# cb_v0.net
KiCad netlist of a schematic drawn in Altium Designer
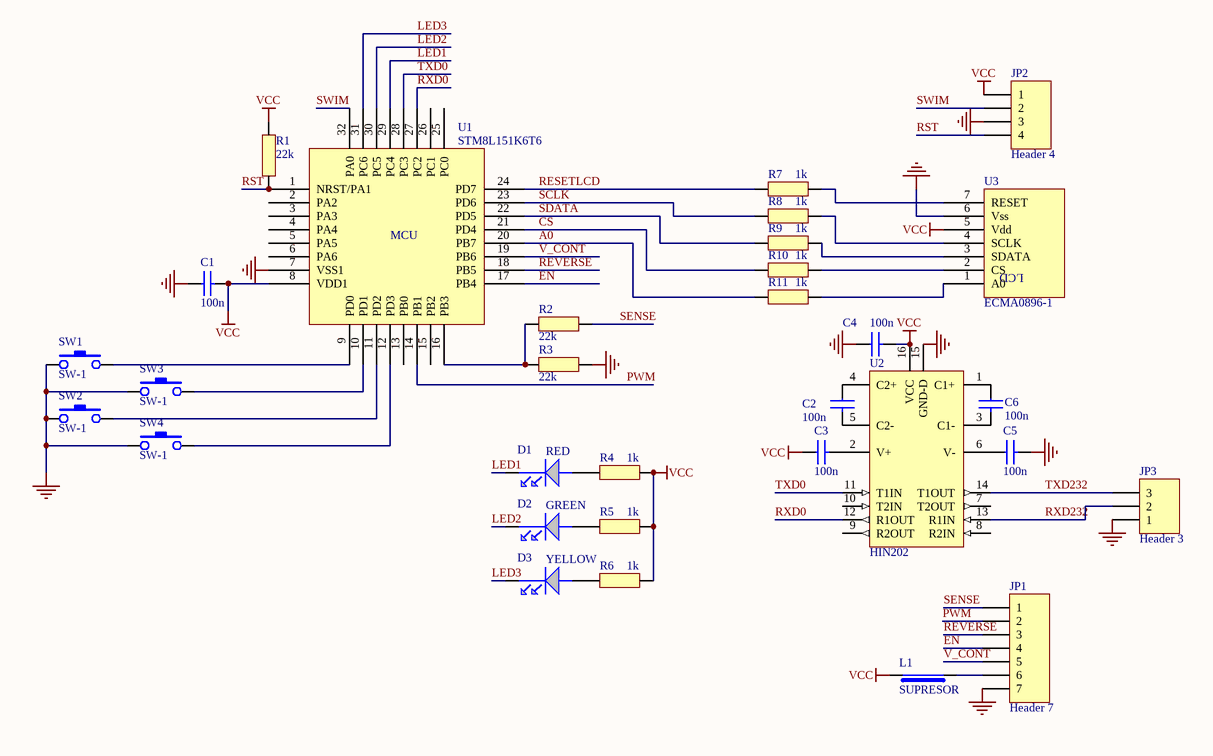
[diagram p0: cb_v0.SchDoc]

(export (version "E")
  (design (tool "Eeschema 10.0.6"))
  (components
    (comp (ref "C1") (value "100n") (footprint "C-0805") (libsource (lib "RCS-Discret") (part "C")))
    (comp (ref "C2") (value "100n") (footprint "C-0805") (libsource (lib "RCS-Discret") (part "C")))
    (comp (ref "C3") (value "100n") (footprint "C-0805") (libsource (lib "RCS-Discret") (part "C")))
    (comp (ref "C4") (value "100n") (footprint "C-0805") (libsource (lib "RCS-Discret") (part "C")))
    (comp (ref "C5") (value "100n") (footprint "C-0805") (libsource (lib "RCS-Discret") (part "C")))
    (comp (ref "C6") (value "100n") (footprint "C-0805") (libsource (lib "RCS-Discret") (part "C")))
    (comp (ref "D1") (value "RED") (footprint "LED-DIP-1") (libsource (lib "RCS-Discret") (part "LED")))
    (comp (ref "D2") (value "GREEN") (footprint "LED-DIP-1") (libsource (lib "RCS-Discret") (part "LED")))
    (comp (ref "D3") (value "YELLOW") (footprint "LED-DIP-1") (libsource (lib "RCS-Discret") (part "LED")))
    (comp (ref "JP1")
      (value "Header 7")
      (footprint "HDR1X7")
      (description "Header, 7-Pin")
      (fields (field (name "PUBLISHER") "Altium Limited"))
      (libsource (lib "Miscellaneous Connectors") (part "Header 7"))
    )
    (comp (ref "JP2")
      (value "Header 4")
      (footprint "HDR1X4")
      (description "Header, 4-Pin")
      (fields (field (name "PUBLISHER") "Altium Limited"))
      (libsource (lib "Miscellaneous Connectors") (part "Header 4"))
    )
    (comp (ref "JP3")
      (value "Header 3")
      (footprint "HDR1X3")
      (description "Header, 3-Pin")
      (fields (field (name "PUBLISHER") "Altium Limited"))
      (libsource (lib "Miscellaneous Connectors") (part "Header 3"))
    )
    (comp (ref "L1")
      (value "SUPRESOR")
      (footprint "R-1206")
      (libsource (lib "RCS-Discret") (part "SUPRESOR"))
    )
    (comp (ref "R1") (value "22k") (footprint "R-0805") (libsource (lib "") (part "R_3")))
    (comp (ref "R2") (value "22k") (footprint "R-0805") (libsource (lib "") (part "R_1")))
    (comp (ref "R3") (value "22k") (footprint "R-0805") (libsource (lib "") (part "R_2")))
    (comp (ref "R4") (value "1k") (footprint "R-0805") (libsource (lib "") (part "R_2")))
    (comp (ref "R5") (value "1k") (footprint "R-0805") (libsource (lib "") (part "R_2")))
    (comp (ref "R6") (value "1k") (footprint "R-0805") (libsource (lib "") (part "R_2")))
    (comp (ref "R7") (value "1k") (footprint "R-0805") (libsource (lib "RCS-Discret") (part "R")))
    (comp (ref "R8") (value "1k") (footprint "R-0805") (libsource (lib "RCS-Discret") (part "R")))
    (comp (ref "R9") (value "1k") (footprint "R-0805") (libsource (lib "RCS-Discret") (part "R")))
    (comp (ref "R10") (value "1k") (footprint "R-0805") (libsource (lib "RCS-Discret") (part "R")))
    (comp (ref "R11") (value "1k") (footprint "R-0805") (libsource (lib "RCS-Discret") (part "R")))
    (comp (ref "SW1")
      (value "SW-1")
      (footprint "SW2mini")
      (libsource (lib "RCS-Connect&pushe") (part "SW-1"))
    )
    (comp (ref "SW2")
      (value "SW-1")
      (footprint "SW2mini")
      (libsource (lib "RCS-Connect&pushe") (part "SW-1"))
    )
    (comp (ref "SW3")
      (value "SW-1")
      (footprint "SW2mini")
      (libsource (lib "RCS-Connect&pushe") (part "SW-1"))
    )
    (comp (ref "SW4")
      (value "SW-1")
      (footprint "SW2mini")
      (libsource (lib "RCS-Connect&pushe") (part "SW-1"))
    )
    (comp (ref "U1")
      (value "STM8L151K6T6")
      (footprint "QFP32")
      (libsource (lib "RCS-IMS") (part "STM32L151"))
    )
    (comp (ref "U2")
      (value "HIN202")
      (footprint "SO16-(SOT-109-1)")
      (description "RS232 driver")
      (libsource (lib "RCS-IMS") (part "HIN202"))
    )
    (comp (ref "U3")
      (value "ECMA0896-1")
      (footprint "ECMA0896")
      (libsource (lib "RCS-IMS") (part "ECMA0896"))
    )
  )
  (nets
    (net (code "1") (name "/A0") (class "Default")
      (node (ref "R11") (pin "1") (pinfunction "1_1") (pintype "passive"))
      (node (ref "U1") (pin "20") (pinfunction "PB7_20") (pintype "passive"))
    )
    (net (code "2") (name "/CS") (class "Default")
      (node (ref "R10") (pin "1") (pinfunction "1_1") (pintype "passive"))
      (node (ref "U1") (pin "21") (pinfunction "PD4_21") (pintype "passive"))
    )
    (net (code "3") (name "/EN") (class "Default")
      (node (ref "JP1") (pin "4") (pinfunction "4_4") (pintype "passive"))
      (node (ref "U1") (pin "17") (pinfunction "PB4_17") (pintype "passive"))
    )
    (net (code "4") (name "/LED1") (class "Default")
      (node (ref "D1") (pin "K") (pinfunction "CATHODE_K") (pintype "passive"))
      (node (ref "U1") (pin "29") (pinfunction "PC4_29") (pintype "passive"))
    )
    (net (code "5") (name "/LED2") (class "Default")
      (node (ref "D2") (pin "K") (pinfunction "CATHODE_K") (pintype "passive"))
      (node (ref "U1") (pin "30") (pinfunction "PC5_30") (pintype "passive"))
    )
    (net (code "6") (name "/LED3") (class "Default")
      (node (ref "D3") (pin "K") (pinfunction "CATHODE_K") (pintype "passive"))
      (node (ref "U1") (pin "31") (pinfunction "PC6_31") (pintype "passive"))
    )
    (net (code "7") (name "/PWM") (class "Default")
      (node (ref "JP1") (pin "2") (pinfunction "2_2") (pintype "passive"))
      (node (ref "U1") (pin "14") (pinfunction "PB1_14") (pintype "passive"))
    )
    (net (code "8") (name "/RESETLCD") (class "Default")
      (node (ref "R7") (pin "1") (pinfunction "1_1") (pintype "passive"))
      (node (ref "U1") (pin "24") (pinfunction "PD7_24") (pintype "passive"))
    )
    (net (code "9") (name "/REVERSE") (class "Default")
      (node (ref "JP1") (pin "3") (pinfunction "3_3") (pintype "passive"))
      (node (ref "U1") (pin "18") (pinfunction "PB5_18") (pintype "passive"))
    )
    (net (code "10") (name "/RST") (class "Default")
      (node (ref "JP2") (pin "4") (pinfunction "4_4") (pintype "passive"))
      (node (ref "R1") (pin "2") (pinfunction "2_2") (pintype "passive"))
      (node (ref "U1") (pin "1") (pinfunction "NRST/PA1_1") (pintype "passive"))
    )
    (net (code "11") (name "/RXD0") (class "Default")
      (node (ref "U1") (pin "27") (pinfunction "PC2_27") (pintype "passive"))
      (node (ref "U2") (pin "12") (pinfunction "R1OUT_12") (pintype "output"))
    )
    (net (code "12") (name "/RXD232") (class "Default")
      (node (ref "JP3") (pin "2") (pinfunction "2_2") (pintype "passive"))
      (node (ref "U2") (pin "13") (pinfunction "R1IN_13") (pintype "input"))
    )
    (net (code "13") (name "/SCLK") (class "Default")
      (node (ref "R8") (pin "1") (pinfunction "1_1") (pintype "passive"))
      (node (ref "U1") (pin "23") (pinfunction "PD6_23") (pintype "passive"))
    )
    (net (code "14") (name "/SDATA") (class "Default")
      (node (ref "R9") (pin "1") (pinfunction "1_1") (pintype "passive"))
      (node (ref "U1") (pin "22") (pinfunction "PD5_22") (pintype "passive"))
    )
    (net (code "15") (name "/SENSE") (class "Default")
      (node (ref "JP1") (pin "1") (pinfunction "1_1") (pintype "passive"))
      (node (ref "R2") (pin "1") (pinfunction "1_1") (pintype "passive"))
    )
    (net (code "16") (name "/SWIM") (class "Default")
      (node (ref "JP2") (pin "2") (pinfunction "2_2") (pintype "passive"))
      (node (ref "U1") (pin "32") (pinfunction "PA0_32") (pintype "passive"))
    )
    (net (code "17") (name "/TXD0") (class "Default")
      (node (ref "U1") (pin "28") (pinfunction "PC3_28") (pintype "passive"))
      (node (ref "U2") (pin "11") (pinfunction "T1IN_11") (pintype "input"))
    )
    (net (code "18") (name "/TXD232") (class "Default")
      (node (ref "JP3") (pin "3") (pinfunction "3_3") (pintype "passive"))
      (node (ref "U2") (pin "14") (pinfunction "T1OUT_14") (pintype "output"))
    )
    (net (code "19") (name "/V_CONT") (class "Default")
      (node (ref "JP1") (pin "5") (pinfunction "5_5") (pintype "passive"))
      (node (ref "U1") (pin "19") (pinfunction "PB6_19") (pintype "passive"))
    )
    (net (code "20") (name "GND") (class "Default")
      (node (ref "C1") (pin "1") (pinfunction "1_1") (pintype "passive"))
      (node (ref "C4") (pin "1") (pinfunction "1_1") (pintype "passive"))
      (node (ref "C5") (pin "2") (pinfunction "2_2") (pintype "passive"))
      (node (ref "JP1") (pin "7") (pinfunction "7_7") (pintype "passive"))
      (node (ref "JP2") (pin "3") (pinfunction "3_3") (pintype "passive"))
      (node (ref "JP3") (pin "1") (pinfunction "1_1") (pintype "passive"))
      (node (ref "R3") (pin "2") (pinfunction "2_2") (pintype "passive"))
      (node (ref "SW1") (pin "2") (pinfunction "2_2") (pintype "passive"))
      (node (ref "SW2") (pin "2") (pinfunction "2_2") (pintype "passive"))
      (node (ref "SW3") (pin "2") (pinfunction "2_2") (pintype "passive"))
      (node (ref "SW4") (pin "2") (pinfunction "2_2") (pintype "passive"))
      (node (ref "U1") (pin "7") (pinfunction "VSS1_7") (pintype "passive"))
      (node (ref "U2") (pin "15") (pinfunction "GND-D_15") (pintype "power_in"))
      (node (ref "U3") (pin "6") (pinfunction "Vss_6") (pintype "passive"))
    )
    (net (code "21") (name "Net-(D1-ANODE)") (class "Default")
      (node (ref "D1") (pin "A") (pinfunction "ANODE_A") (pintype "passive"))
      (node (ref "R4") (pin "1") (pinfunction "1_1") (pintype "passive"))
    )
    (net (code "22") (name "Net-(D2-ANODE)") (class "Default")
      (node (ref "D2") (pin "A") (pinfunction "ANODE_A") (pintype "passive"))
      (node (ref "R5") (pin "1") (pinfunction "1_1") (pintype "passive"))
    )
    (net (code "23") (name "Net-(D3-ANODE)") (class "Default")
      (node (ref "D3") (pin "A") (pinfunction "ANODE_A") (pintype "passive"))
      (node (ref "R6") (pin "1") (pinfunction "1_1") (pintype "passive"))
    )
    (net (code "24") (name "Net-(JP1-Pad6)") (class "Default")
      (node (ref "JP1") (pin "6") (pinfunction "6_6") (pintype "passive"))
      (node (ref "L1") (pin "1") (pinfunction "1_1") (pintype "passive"))
    )
    (net (code "25") (name "Net-(U1-PB3)") (class "Default")
      (node (ref "R2") (pin "2") (pinfunction "2_2") (pintype "passive"))
      (node (ref "R3") (pin "1") (pinfunction "1_1") (pintype "passive"))
      (node (ref "U1") (pin "16") (pinfunction "PB3_16") (pintype "passive"))
    )
    (net (code "26") (name "Net-(U1-PD0)") (class "Default")
      (node (ref "SW1") (pin "1") (pinfunction "1_1") (pintype "passive"))
      (node (ref "U1") (pin "9") (pinfunction "PD0_9") (pintype "passive"))
    )
    (net (code "27") (name "Net-(U1-PD1)") (class "Default")
      (node (ref "SW3") (pin "1") (pinfunction "1_1") (pintype "passive"))
      (node (ref "U1") (pin "10") (pinfunction "PD1_10") (pintype "passive"))
    )
    (net (code "28") (name "Net-(U1-PD2)") (class "Default")
      (node (ref "SW2") (pin "1") (pinfunction "1_1") (pintype "passive"))
      (node (ref "U1") (pin "11") (pinfunction "PD2_11") (pintype "passive"))
    )
    (net (code "29") (name "Net-(U1-PD3)") (class "Default")
      (node (ref "SW4") (pin "1") (pinfunction "1_1") (pintype "passive"))
      (node (ref "U1") (pin "12") (pinfunction "PD3_12") (pintype "passive"))
    )
    (net (code "30") (name "Net-(U2-C1+)") (class "Default")
      (node (ref "C6") (pin "1") (pinfunction "1_1") (pintype "passive"))
      (node (ref "U2") (pin "1") (pinfunction "C1+_1") (pintype "passive"))
    )
    (net (code "31") (name "Net-(U2-C1-)") (class "Default")
      (node (ref "C6") (pin "2") (pinfunction "2_2") (pintype "passive"))
      (node (ref "U2") (pin "3") (pinfunction "C1-_3") (pintype "passive"))
    )
    (net (code "32") (name "Net-(U2-C2+)") (class "Default")
      (node (ref "C2") (pin "1") (pinfunction "1_1") (pintype "passive"))
      (node (ref "U2") (pin "4") (pinfunction "C2+_4") (pintype "passive"))
    )
    (net (code "33") (name "Net-(U2-C2-)") (class "Default")
      (node (ref "C2") (pin "2") (pinfunction "2_2") (pintype "passive"))
      (node (ref "U2") (pin "5") (pinfunction "C2-_5") (pintype "passive"))
    )
    (net (code "34") (name "Net-(U2-V+)") (class "Default")
      (node (ref "C3") (pin "2") (pinfunction "2_2") (pintype "passive"))
      (node (ref "U2") (pin "2") (pinfunction "V+_2") (pintype "passive"))
    )
    (net (code "35") (name "Net-(U2-V-)") (class "Default")
      (node (ref "C5") (pin "1") (pinfunction "1_1") (pintype "passive"))
      (node (ref "U2") (pin "6") (pinfunction "V-_6") (pintype "passive"))
    )
    (net (code "36") (name "Net-(U3-A0)") (class "Default")
      (node (ref "R11") (pin "2") (pinfunction "2_2") (pintype "passive"))
      (node (ref "U3") (pin "1") (pinfunction "A0_1") (pintype "passive"))
    )
    (net (code "37") (name "Net-(U3-CS)") (class "Default")
      (node (ref "R10") (pin "2") (pinfunction "2_2") (pintype "passive"))
      (node (ref "U3") (pin "2") (pinfunction "CS_2") (pintype "passive"))
    )
    (net (code "38") (name "Net-(U3-RESET)") (class "Default")
      (node (ref "R7") (pin "2") (pinfunction "2_2") (pintype "passive"))
      (node (ref "U3") (pin "7") (pinfunction "RESET_7") (pintype "passive"))
    )
    (net (code "39") (name "Net-(U3-SCLK)") (class "Default")
      (node (ref "R8") (pin "2") (pinfunction "2_2") (pintype "passive"))
      (node (ref "U3") (pin "4") (pinfunction "SCLK_4") (pintype "passive"))
    )
    (net (code "40") (name "Net-(U3-SDATA)") (class "Default")
      (node (ref "R9") (pin "2") (pinfunction "2_2") (pintype "passive"))
      (node (ref "U3") (pin "3") (pinfunction "SDATA_3") (pintype "passive"))
    )
    (net (code "41") (name "VCC") (class "Default")
      (node (ref "C1") (pin "2") (pinfunction "2_2") (pintype "passive"))
      (node (ref "C3") (pin "1") (pinfunction "1_1") (pintype "passive"))
      (node (ref "C4") (pin "2") (pinfunction "2_2") (pintype "passive"))
      (node (ref "JP2") (pin "1") (pinfunction "1_1") (pintype "passive"))
      (node (ref "L1") (pin "2") (pinfunction "2_2") (pintype "passive"))
      (node (ref "R1") (pin "1") (pinfunction "1_1") (pintype "passive"))
      (node (ref "R4") (pin "2") (pinfunction "2_2") (pintype "passive"))
      (node (ref "R5") (pin "2") (pinfunction "2_2") (pintype "passive"))
      (node (ref "R6") (pin "2") (pinfunction "2_2") (pintype "passive"))
      (node (ref "U1") (pin "8") (pinfunction "VDD1_8") (pintype "passive"))
      (node (ref "U2") (pin "16") (pinfunction "VCC_16") (pintype "power_in"))
      (node (ref "U3") (pin "5") (pinfunction "Vdd_5") (pintype "passive"))
    )
    (net (code "42") (name "unconnected-(U1-PA2-Pad2)") (class "Default")
      (node (ref "U1") (pin "2") (pinfunction "PA2_2") (pintype "passive"))
    )
    (net (code "43") (name "unconnected-(U1-PA3-Pad3)") (class "Default")
      (node (ref "U1") (pin "3") (pinfunction "PA3_3") (pintype "passive"))
    )
    (net (code "44") (name "unconnected-(U1-PA4-Pad4)") (class "Default")
      (node (ref "U1") (pin "4") (pinfunction "PA4_4") (pintype "passive"))
    )
    (net (code "45") (name "unconnected-(U1-PA5-Pad5)") (class "Default")
      (node (ref "U1") (pin "5") (pinfunction "PA5_5") (pintype "passive"))
    )
    (net (code "46") (name "unconnected-(U1-PA6-Pad6)") (class "Default")
      (node (ref "U1") (pin "6") (pinfunction "PA6_6") (pintype "passive"))
    )
    (net (code "47") (name "unconnected-(U1-PB0-Pad13)") (class "Default")
      (node (ref "U1") (pin "13") (pinfunction "PB0_13") (pintype "passive"))
    )
    (net (code "48") (name "unconnected-(U1-PB2-Pad15)") (class "Default")
      (node (ref "U1") (pin "15") (pinfunction "PB2_15") (pintype "passive"))
    )
    (net (code "49") (name "unconnected-(U1-PC0-Pad25)") (class "Default")
      (node (ref "U1") (pin "25") (pinfunction "PC0_25") (pintype "passive"))
    )
    (net (code "50") (name "unconnected-(U1-PC1-Pad26)") (class "Default")
      (node (ref "U1") (pin "26") (pinfunction "PC1_26") (pintype "passive"))
    )
    (net (code "51") (name "unconnected-(U2-R2IN-Pad8)") (class "Default")
      (node (ref "U2") (pin "8") (pinfunction "R2IN_8") (pintype "input"))
    )
    (net (code "52") (name "unconnected-(U2-R2OUT-Pad9)") (class "Default")
      (node (ref "U2") (pin "9") (pinfunction "R2OUT_9") (pintype "output"))
    )
    (net (code "53") (name "unconnected-(U2-T2IN-Pad10)") (class "Default")
      (node (ref "U2") (pin "10") (pinfunction "T2IN_10") (pintype "input"))
    )
    (net (code "54") (name "unconnected-(U2-T2OUT-Pad7)") (class "Default")
      (node (ref "U2") (pin "7") (pinfunction "T2OUT_7") (pintype "output"))
    )
  )
)
